# 780-00059revB_-_SCH_Sinistro_Camera_Cont.net
KiCad netlist of a schematic drawn in Altium Designer
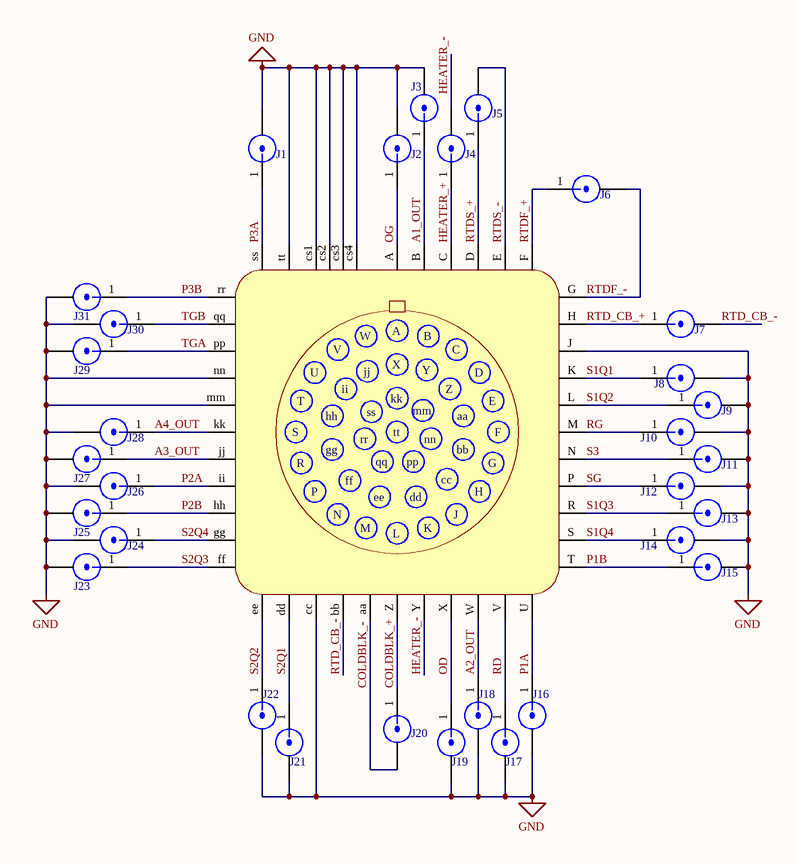
[diagram p0: 780-00059revB - SCH, Sinistro Camera Controller Extension.SchDoc]

(export (version "E")
  (design (tool "Eeschema 10.0.6"))
  (components
    (comp (ref "J1")
      (value "RG-178_CoaxTermination")
      (footprint "RG-178_TERMINATION")
      (description "Coax termination")
      (libsource (lib "ImagingLabLibrary") (part "RG-178_CoaxTermination"))
    )
    (comp (ref "J2")
      (value "RG-178_CoaxTermination")
      (footprint "RG-178_TERMINATION")
      (libsource (lib "ImagingLabLibrary") (part "RG-178_CoaxTermination"))
    )
    (comp (ref "J3")
      (value "RG-178_CoaxTermination")
      (footprint "RG-178_TERMINATION")
      (libsource (lib "ImagingLabLibrary") (part "RG-178_CoaxTermination"))
    )
    (comp (ref "J4")
      (value "RG-178_CoaxTermination")
      (footprint "RG-178_TERMINATION")
      (libsource (lib "ImagingLabLibrary") (part "RG-178_CoaxTermination"))
    )
    (comp (ref "J5")
      (value "RG-178_CoaxTermination")
      (footprint "RG-178_TERMINATION")
      (libsource (lib "ImagingLabLibrary") (part "RG-178_CoaxTermination"))
    )
    (comp (ref "J6")
      (value "RG-178_CoaxTermination")
      (footprint "RG-178_TERMINATION")
      (libsource (lib "ImagingLabLibrary") (part "RG-178_CoaxTermination"))
    )
    (comp (ref "J7")
      (value "RG-178_CoaxTermination")
      (footprint "RG-178_TERMINATION")
      (libsource (lib "ImagingLabLibrary") (part "RG-178_CoaxTermination"))
    )
    (comp (ref "J8")
      (value "RG-178_CoaxTermination")
      (footprint "RG-178_TERMINATION")
      (libsource (lib "ImagingLabLibrary") (part "RG-178_CoaxTermination"))
    )
    (comp (ref "J9")
      (value "RG-178_CoaxTermination")
      (footprint "RG-178_TERMINATION")
      (libsource (lib "ImagingLabLibrary") (part "RG-178_CoaxTermination"))
    )
    (comp (ref "J10")
      (value "RG-178_CoaxTermination")
      (footprint "RG-178_TERMINATION")
      (libsource (lib "ImagingLabLibrary") (part "RG-178_CoaxTermination"))
    )
    (comp (ref "J11")
      (value "RG-178_CoaxTermination")
      (footprint "RG-178_TERMINATION")
      (libsource (lib "ImagingLabLibrary") (part "RG-178_CoaxTermination"))
    )
    (comp (ref "J12")
      (value "RG-178_CoaxTermination")
      (footprint "RG-178_TERMINATION")
      (libsource (lib "ImagingLabLibrary") (part "RG-178_CoaxTermination"))
    )
    (comp (ref "J13")
      (value "RG-178_CoaxTermination")
      (footprint "RG-178_TERMINATION")
      (libsource (lib "ImagingLabLibrary") (part "RG-178_CoaxTermination"))
    )
    (comp (ref "J14")
      (value "RG-178_CoaxTermination")
      (footprint "RG-178_TERMINATION")
      (libsource (lib "ImagingLabLibrary") (part "RG-178_CoaxTermination"))
    )
    (comp (ref "J15")
      (value "RG-178_CoaxTermination")
      (footprint "RG-178_TERMINATION")
      (libsource (lib "ImagingLabLibrary") (part "RG-178_CoaxTermination"))
    )
    (comp (ref "J16")
      (value "RG-178_CoaxTermination")
      (footprint "RG-178_TERMINATION")
      (libsource (lib "ImagingLabLibrary") (part "RG-178_CoaxTermination"))
    )
    (comp (ref "J17")
      (value "RG-178_CoaxTermination")
      (footprint "RG-178_TERMINATION")
      (libsource (lib "ImagingLabLibrary") (part "RG-178_CoaxTermination"))
    )
    (comp (ref "J18")
      (value "RG-178_CoaxTermination")
      (footprint "RG-178_TERMINATION")
      (libsource (lib "ImagingLabLibrary") (part "RG-178_CoaxTermination"))
    )
    (comp (ref "J19")
      (value "RG-178_CoaxTermination")
      (footprint "RG-178_TERMINATION")
      (libsource (lib "ImagingLabLibrary") (part "RG-178_CoaxTermination"))
    )
    (comp (ref "J20")
      (value "RG-178_CoaxTermination")
      (footprint "RG-178_TERMINATION")
      (libsource (lib "ImagingLabLibrary") (part "RG-178_CoaxTermination"))
    )
    (comp (ref "J21")
      (value "RG-178_CoaxTermination")
      (footprint "RG-178_TERMINATION")
      (libsource (lib "ImagingLabLibrary") (part "RG-178_CoaxTermination"))
    )
    (comp (ref "J22")
      (value "RG-178_CoaxTermination")
      (footprint "RG-178_TERMINATION")
      (libsource (lib "ImagingLabLibrary") (part "RG-178_CoaxTermination"))
    )
    (comp (ref "J23")
      (value "RG-178_CoaxTermination")
      (footprint "RG-178_TERMINATION")
      (libsource (lib "ImagingLabLibrary") (part "RG-178_CoaxTermination"))
    )
    (comp (ref "J24")
      (value "RG-178_CoaxTermination")
      (footprint "RG-178_TERMINATION")
      (libsource (lib "ImagingLabLibrary") (part "RG-178_CoaxTermination"))
    )
    (comp (ref "J25")
      (value "RG-178_CoaxTermination")
      (footprint "RG-178_TERMINATION")
      (libsource (lib "ImagingLabLibrary") (part "RG-178_CoaxTermination"))
    )
    (comp (ref "J26")
      (value "RG-178_CoaxTermination")
      (footprint "RG-178_TERMINATION")
      (libsource (lib "ImagingLabLibrary") (part "RG-178_CoaxTermination"))
    )
    (comp (ref "J27")
      (value "RG-178_CoaxTermination")
      (footprint "RG-178_TERMINATION")
      (libsource (lib "ImagingLabLibrary") (part "RG-178_CoaxTermination"))
    )
    (comp (ref "J28")
      (value "RG-178_CoaxTermination")
      (footprint "RG-178_TERMINATION")
      (libsource (lib "ImagingLabLibrary") (part "RG-178_CoaxTermination"))
    )
    (comp (ref "J29")
      (value "RG-178_CoaxTermination")
      (footprint "RG-178_TERMINATION")
      (libsource (lib "ImagingLabLibrary") (part "RG-178_CoaxTermination"))
    )
    (comp (ref "J30")
      (value "RG-178_CoaxTermination")
      (footprint "RG-178_TERMINATION")
      (libsource (lib "ImagingLabLibrary") (part "RG-178_CoaxTermination"))
    )
    (comp (ref "J31")
      (value "RG-178_CoaxTermination")
      (footprint "RG-178_TERMINATION")
      (libsource (lib "ImagingLabLibrary") (part "RG-178_CoaxTermination"))
    )
    (comp (ref "P1")
      (value "125-00409 - MIL-DTL-26482 20-41 Pins, Jam nut")
      (footprint "MS-3116 Size 20-41, Male")
      (libsource (lib "ImagingLabLibrary") (part "125-00409 - MIL-DTL-26482 20-41 Pins, Jam nut"))
    )
  )
  (nets
    (net (code "1") (name "/A1_OUT") (class "Default")
      (node (ref "J3") (pin "1") (pinfunction "1_1") (pintype "passive"))
      (node (ref "P1") (pin "B") (pinfunction "B_B") (pintype "passive"))
    )
    (net (code "2") (name "/A2_OUT") (class "Default")
      (node (ref "J18") (pin "1") (pinfunction "1_1") (pintype "passive"))
      (node (ref "P1") (pin "W") (pinfunction "W_W") (pintype "passive"))
    )
    (net (code "3") (name "/A3_OUT") (class "Default")
      (node (ref "J27") (pin "1") (pinfunction "1_1") (pintype "passive"))
      (node (ref "P1") (pin "jj") (pinfunction "jj_jj") (pintype "passive"))
    )
    (net (code "4") (name "/A4_OUT") (class "Default")
      (node (ref "J28") (pin "1") (pinfunction "1_1") (pintype "passive"))
      (node (ref "P1") (pin "kk") (pinfunction "kk_kk") (pintype "passive"))
    )
    (net (code "5") (name "/COLDBLK_+") (class "Default")
      (node (ref "J20") (pin "1") (pinfunction "1_1") (pintype "passive"))
      (node (ref "P1") (pin "Z") (pinfunction "Z_Z") (pintype "passive"))
    )
    (net (code "6") (name "/COLDBLK_-") (class "Default")
      (node (ref "J20") (pin "GND") (pinfunction "GND_GND") (pintype "passive"))
      (node (ref "P1") (pin "aa") (pinfunction "aa_aa") (pintype "passive"))
    )
    (net (code "7") (name "/HEATER_+") (class "Default")
      (node (ref "J4") (pin "1") (pinfunction "1_1") (pintype "passive"))
      (node (ref "P1") (pin "C") (pinfunction "C_C") (pintype "passive"))
    )
    (net (code "8") (name "/HEATER_-") (class "Default")
      (node (ref "J4") (pin "GND") (pinfunction "GND_GND") (pintype "passive"))
      (node (ref "P1") (pin "Y") (pinfunction "Y_Y") (pintype "passive"))
    )
    (net (code "9") (name "/OD") (class "Default")
      (node (ref "J19") (pin "1") (pinfunction "1_1") (pintype "passive"))
      (node (ref "P1") (pin "X") (pinfunction "X_X") (pintype "passive"))
    )
    (net (code "10") (name "/OG") (class "Default")
      (node (ref "J2") (pin "1") (pinfunction "1_1") (pintype "passive"))
      (node (ref "P1") (pin "A") (pinfunction "A_A") (pintype "passive"))
    )
    (net (code "11") (name "/P1A") (class "Default")
      (node (ref "J16") (pin "1") (pinfunction "1_1") (pintype "passive"))
      (node (ref "P1") (pin "U") (pinfunction "U_U") (pintype "passive"))
    )
    (net (code "12") (name "/P1B") (class "Default")
      (node (ref "J15") (pin "1") (pinfunction "1_1") (pintype "passive"))
      (node (ref "P1") (pin "T") (pinfunction "T_T") (pintype "passive"))
    )
    (net (code "13") (name "/P2A") (class "Default")
      (node (ref "J26") (pin "1") (pinfunction "1_1") (pintype "passive"))
      (node (ref "P1") (pin "ii") (pinfunction "ii_ii") (pintype "passive"))
    )
    (net (code "14") (name "/P2B") (class "Default")
      (node (ref "J25") (pin "1") (pinfunction "1_1") (pintype "passive"))
      (node (ref "P1") (pin "hh") (pinfunction "hh_hh") (pintype "passive"))
    )
    (net (code "15") (name "/P3A") (class "Default")
      (node (ref "J1") (pin "1") (pinfunction "1_1") (pintype "passive"))
      (node (ref "P1") (pin "ss") (pinfunction "ss_ss") (pintype "passive"))
    )
    (net (code "16") (name "/P3B") (class "Default")
      (node (ref "J31") (pin "1") (pinfunction "1_1") (pintype "passive"))
      (node (ref "P1") (pin "rr") (pinfunction "rr_rr") (pintype "passive"))
    )
    (net (code "17") (name "/RD") (class "Default")
      (node (ref "J17") (pin "1") (pinfunction "1_1") (pintype "passive"))
      (node (ref "P1") (pin "V") (pinfunction "V_V") (pintype "passive"))
    )
    (net (code "18") (name "/RG") (class "Default")
      (node (ref "J10") (pin "1") (pinfunction "1_1") (pintype "passive"))
      (node (ref "P1") (pin "M") (pinfunction "M_M") (pintype "passive"))
    )
    (net (code "19") (name "/RTDF_+") (class "Default")
      (node (ref "J6") (pin "1") (pinfunction "1_1") (pintype "passive"))
      (node (ref "P1") (pin "F") (pinfunction "F_F") (pintype "passive"))
    )
    (net (code "20") (name "/RTDF_-") (class "Default")
      (node (ref "J6") (pin "GND") (pinfunction "GND_GND") (pintype "passive"))
      (node (ref "P1") (pin "G") (pinfunction "G_G") (pintype "passive"))
    )
    (net (code "21") (name "/RTDS_+") (class "Default")
      (node (ref "J5") (pin "1") (pinfunction "1_1") (pintype "passive"))
      (node (ref "P1") (pin "D") (pinfunction "D_D") (pintype "passive"))
    )
    (net (code "22") (name "/RTDS_-") (class "Default")
      (node (ref "J5") (pin "GND") (pinfunction "GND_GND") (pintype "passive"))
      (node (ref "P1") (pin "E") (pinfunction "E_E") (pintype "passive"))
    )
    (net (code "23") (name "/RTD_CB_+") (class "Default")
      (node (ref "J7") (pin "1") (pinfunction "1_1") (pintype "passive"))
      (node (ref "P1") (pin "H") (pinfunction "H_H") (pintype "passive"))
    )
    (net (code "24") (name "/RTD_CB_-") (class "Default")
      (node (ref "J7") (pin "GND") (pinfunction "GND_GND") (pintype "passive"))
      (node (ref "P1") (pin "bb") (pinfunction "bb_bb") (pintype "passive"))
    )
    (net (code "25") (name "/S1Q1") (class "Default")
      (node (ref "J8") (pin "1") (pinfunction "1_1") (pintype "passive"))
      (node (ref "P1") (pin "K") (pinfunction "K_K") (pintype "passive"))
    )
    (net (code "26") (name "/S1Q2") (class "Default")
      (node (ref "J9") (pin "1") (pinfunction "1_1") (pintype "passive"))
      (node (ref "P1") (pin "L") (pinfunction "L_L") (pintype "passive"))
    )
    (net (code "27") (name "/S1Q3") (class "Default")
      (node (ref "J13") (pin "1") (pinfunction "1_1") (pintype "passive"))
      (node (ref "P1") (pin "R") (pinfunction "R_R") (pintype "passive"))
    )
    (net (code "28") (name "/S1Q4") (class "Default")
      (node (ref "J14") (pin "1") (pinfunction "1_1") (pintype "passive"))
      (node (ref "P1") (pin "S") (pinfunction "S_S") (pintype "passive"))
    )
    (net (code "29") (name "/S2Q1") (class "Default")
      (node (ref "J21") (pin "1") (pinfunction "1_1") (pintype "passive"))
      (node (ref "P1") (pin "dd") (pinfunction "dd_dd") (pintype "passive"))
    )
    (net (code "30") (name "/S2Q2") (class "Default")
      (node (ref "J22") (pin "1") (pinfunction "1_1") (pintype "passive"))
      (node (ref "P1") (pin "ee") (pinfunction "ee_ee") (pintype "passive"))
    )
    (net (code "31") (name "/S2Q3") (class "Default")
      (node (ref "J23") (pin "1") (pinfunction "1_1") (pintype "passive"))
      (node (ref "P1") (pin "ff") (pinfunction "ff_ff") (pintype "passive"))
    )
    (net (code "32") (name "/S2Q4") (class "Default")
      (node (ref "J24") (pin "1") (pinfunction "1_1") (pintype "passive"))
      (node (ref "P1") (pin "gg") (pinfunction "gg_gg") (pintype "passive"))
    )
    (net (code "33") (name "/S3") (class "Default")
      (node (ref "J11") (pin "1") (pinfunction "1_1") (pintype "passive"))
      (node (ref "P1") (pin "N") (pinfunction "N_N") (pintype "passive"))
    )
    (net (code "34") (name "/SG") (class "Default")
      (node (ref "J12") (pin "1") (pinfunction "1_1") (pintype "passive"))
      (node (ref "P1") (pin "P") (pinfunction "P_P") (pintype "passive"))
    )
    (net (code "35") (name "/TGA") (class "Default")
      (node (ref "J29") (pin "1") (pinfunction "1_1") (pintype "passive"))
      (node (ref "P1") (pin "pp") (pinfunction "pp_pp") (pintype "passive"))
    )
    (net (code "36") (name "/TGB") (class "Default")
      (node (ref "J30") (pin "1") (pinfunction "1_1") (pintype "passive"))
      (node (ref "P1") (pin "qq") (pinfunction "qq_qq") (pintype "passive"))
    )
    (net (code "37") (name "GND") (class "Default")
      (node (ref "J1") (pin "GND") (pinfunction "GND_GND") (pintype "passive"))
      (node (ref "J10") (pin "GND") (pinfunction "GND_GND") (pintype "passive"))
      (node (ref "J11") (pin "GND") (pinfunction "GND_GND") (pintype "passive"))
      (node (ref "J12") (pin "GND") (pinfunction "GND_GND") (pintype "passive"))
      (node (ref "J13") (pin "GND") (pinfunction "GND_GND") (pintype "passive"))
      (node (ref "J14") (pin "GND") (pinfunction "GND_GND") (pintype "passive"))
      (node (ref "J15") (pin "GND") (pinfunction "GND_GND") (pintype "passive"))
      (node (ref "J16") (pin "GND") (pinfunction "GND_GND") (pintype "passive"))
      (node (ref "J17") (pin "GND") (pinfunction "GND_GND") (pintype "passive"))
      (node (ref "J18") (pin "GND") (pinfunction "GND_GND") (pintype "passive"))
      (node (ref "J19") (pin "GND") (pinfunction "GND_GND") (pintype "passive"))
      (node (ref "J2") (pin "GND") (pinfunction "GND_GND") (pintype "passive"))
      (node (ref "J21") (pin "GND") (pinfunction "GND_GND") (pintype "passive"))
      (node (ref "J22") (pin "GND") (pinfunction "GND_GND") (pintype "passive"))
      (node (ref "J23") (pin "GND") (pinfunction "GND_GND") (pintype "passive"))
      (node (ref "J24") (pin "GND") (pinfunction "GND_GND") (pintype "passive"))
      (node (ref "J25") (pin "GND") (pinfunction "GND_GND") (pintype "passive"))
      (node (ref "J26") (pin "GND") (pinfunction "GND_GND") (pintype "passive"))
      (node (ref "J27") (pin "GND") (pinfunction "GND_GND") (pintype "passive"))
      (node (ref "J28") (pin "GND") (pinfunction "GND_GND") (pintype "passive"))
      (node (ref "J29") (pin "GND") (pinfunction "GND_GND") (pintype "passive"))
      (node (ref "J3") (pin "GND") (pinfunction "GND_GND") (pintype "passive"))
      (node (ref "J30") (pin "GND") (pinfunction "GND_GND") (pintype "passive"))
      (node (ref "J31") (pin "GND") (pinfunction "GND_GND") (pintype "passive"))
      (node (ref "J8") (pin "GND") (pinfunction "GND_GND") (pintype "passive"))
      (node (ref "J9") (pin "GND") (pinfunction "GND_GND") (pintype "passive"))
      (node (ref "P1") (pin "J") (pinfunction "J_J") (pintype "passive"))
      (node (ref "P1") (pin "cc") (pinfunction "cc_cc") (pintype "passive"))
      (node (ref "P1") (pin "cs1") (pinfunction "cs1_cs1") (pintype "passive"))
      (node (ref "P1") (pin "cs2") (pinfunction "cs2_cs2") (pintype "passive"))
      (node (ref "P1") (pin "cs3") (pinfunction "cs3_cs3") (pintype "passive"))
      (node (ref "P1") (pin "cs4") (pinfunction "cs4_cs4") (pintype "passive"))
      (node (ref "P1") (pin "mm") (pinfunction "mm_mm") (pintype "passive"))
      (node (ref "P1") (pin "nn") (pinfunction "nn_nn") (pintype "passive"))
      (node (ref "P1") (pin "tt") (pinfunction "tt_tt") (pintype "passive"))
    )
  )
)
